# door_light.net
KiCad netlist of a schematic drawn in EAGLE
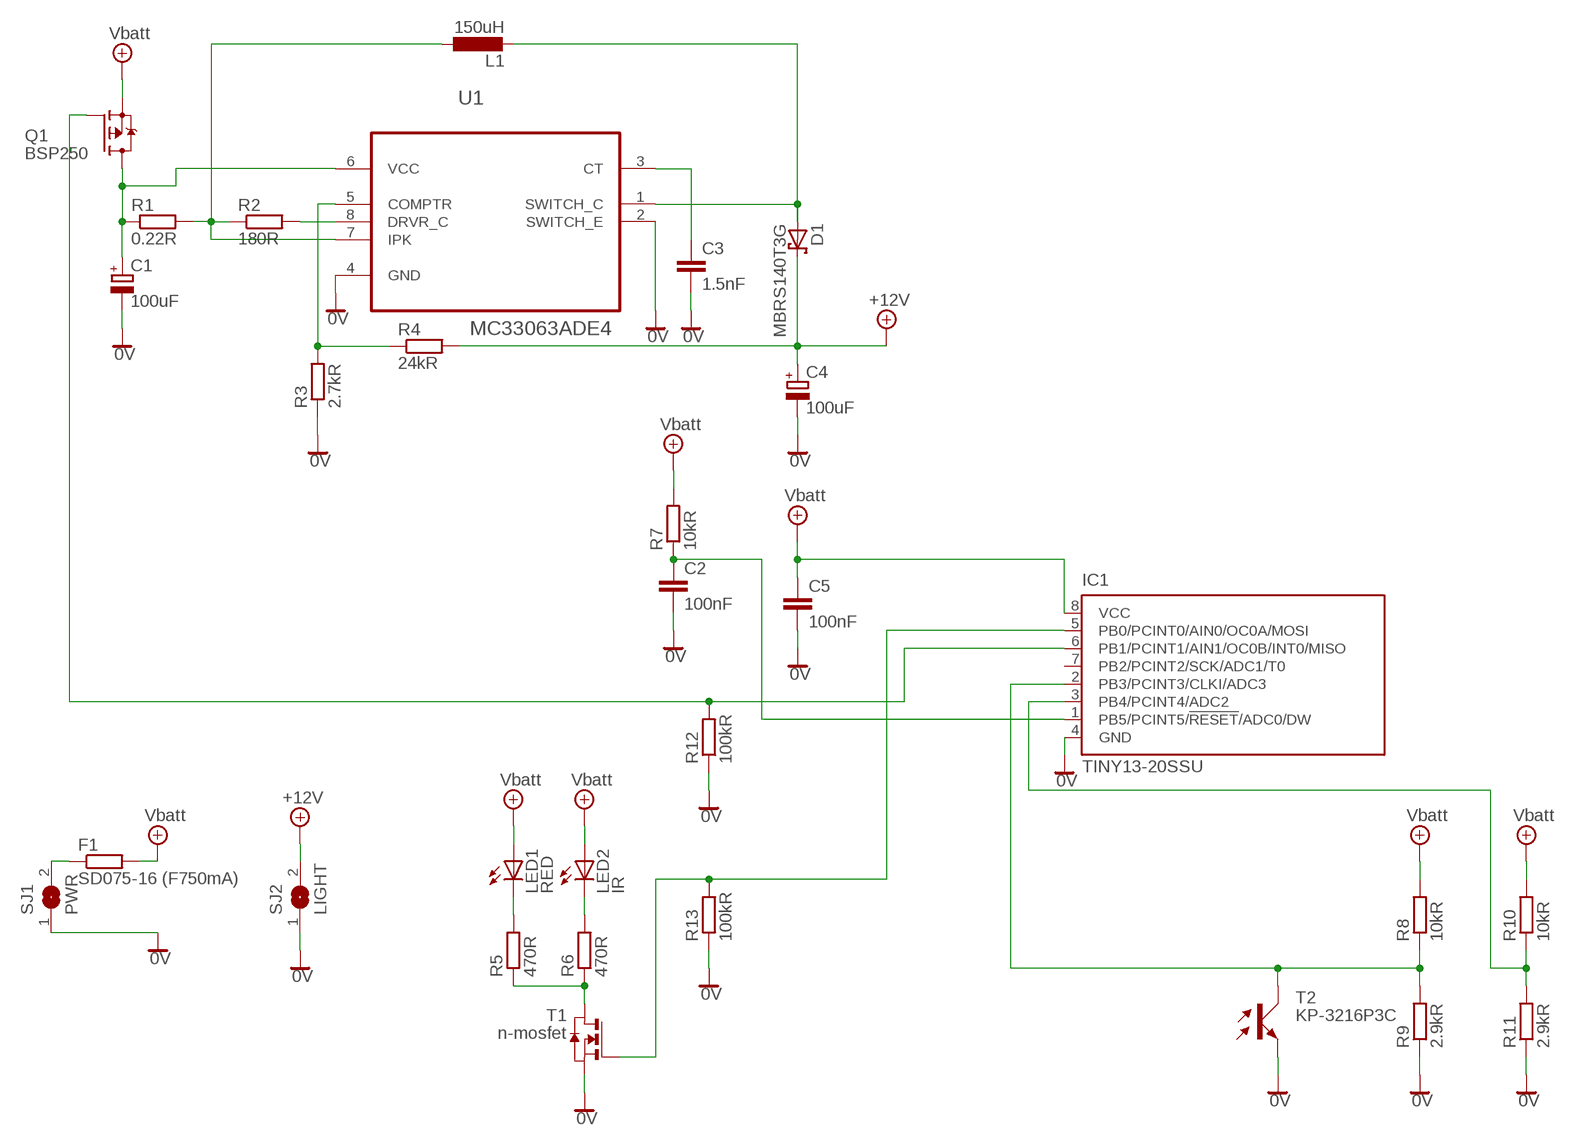
[diagram p0: schematic, sheet 1]

(export (version "E")
  (design (tool "Eeschema 10.0.6"))
  (components
    (comp (ref "C1")
      (value "100uF")
      (footprint "eagle-import:153CLV-0810")
      (libsource (lib "eagle-import") (part "CPOL-EU153CLV-0810"))
    )
    (comp (ref "C2")
      (value "100nF")
      (footprint "eagle-import:C1206")
      (libsource (lib "eagle-import") (part "C-EUC1206"))
    )
    (comp (ref "C3")
      (value "1.5nF")
      (footprint "eagle-import:C1206")
      (libsource (lib "eagle-import") (part "C-EUC1206"))
    )
    (comp (ref "C4")
      (value "100uF")
      (footprint "eagle-import:153CLV-0810")
      (libsource (lib "eagle-import") (part "CPOL-EU153CLV-0810"))
    )
    (comp (ref "C5")
      (value "100nF")
      (footprint "eagle-import:C1206")
      (libsource (lib "eagle-import") (part "C-EUC1206"))
    )
    (comp (ref "D1")
      (value "MBRS140T3G")
      (footprint "eagle-import:SMB")
      (libsource (lib "eagle-import") (part "MBRS130LT3"))
    )
    (comp (ref "F1")
      (value "SD075-16 (F750mA)")
      (footprint "eagle-import:MINI_MELF-0207W")
      (libsource (lib "eagle-import") (part "R-EU_MELF0207W"))
    )
    (comp (ref "IC1")
      (value "TINY13-20SSU")
      (footprint "eagle-import:8S1")
      (fields (field (name "MPN") "ATTINY13-20SSU"))
      (libsource (lib "eagle-import") (part "TINY13SSU-20"))
    )
    (comp (ref "L1")
      (value "150uH")
      (footprint "eagle-import:PIS2816")
      (libsource (lib "eagle-import") (part "L-EUPIS2816"))
    )
    (comp (ref "LED1")
      (value "RED")
      (footprint "eagle-import:CHIPLED_0603")
      (libsource (lib "eagle-import") (part "LEDCHIPLED_0603"))
    )
    (comp (ref "LED2")
      (value "IR")
      (footprint "eagle-import:CHIPLED_1206")
      (libsource (lib "eagle-import") (part "LEDCHIPLED_1206"))
    )
    (comp (ref "Q1")
      (value "BSP250")
      (footprint "eagle-import:SOT223")
      (libsource (lib "eagle-import") (part "BSP170P"))
    )
    (comp (ref "R1")
      (value "0.22R")
      (footprint "eagle-import:M1206")
      (libsource (lib "eagle-import") (part "R-EU_M1206"))
    )
    (comp (ref "R2")
      (value "180R")
      (footprint "eagle-import:R0603")
      (libsource (lib "eagle-import") (part "R-EU_R0603"))
    )
    (comp (ref "R3")
      (value "2.7kR")
      (footprint "eagle-import:R0603")
      (libsource (lib "eagle-import") (part "R-EU_R0603"))
    )
    (comp (ref "R4")
      (value "24kR")
      (footprint "eagle-import:R0603")
      (libsource (lib "eagle-import") (part "R-EU_R0603"))
    )
    (comp (ref "R5")
      (value "470R")
      (footprint "eagle-import:R0603")
      (libsource (lib "eagle-import") (part "R-EU_R0603"))
    )
    (comp (ref "R6")
      (value "470R")
      (footprint "eagle-import:R0603")
      (libsource (lib "eagle-import") (part "R-EU_R0603"))
    )
    (comp (ref "R7")
      (value "10kR")
      (footprint "eagle-import:R0402")
      (libsource (lib "eagle-import") (part "R-EU_R0402"))
    )
    (comp (ref "R8")
      (value "10kR")
      (footprint "eagle-import:R0603")
      (libsource (lib "eagle-import") (part "R-EU_R0603"))
    )
    (comp (ref "R9")
      (value "2.9kR")
      (footprint "eagle-import:R0603")
      (libsource (lib "eagle-import") (part "R-EU_R0603"))
    )
    (comp (ref "R10")
      (value "10kR")
      (footprint "eagle-import:R0603")
      (libsource (lib "eagle-import") (part "R-EU_R0603"))
    )
    (comp (ref "R11")
      (value "2.9kR")
      (footprint "eagle-import:R0603")
      (libsource (lib "eagle-import") (part "R-EU_R0603"))
    )
    (comp (ref "R12")
      (value "100kR")
      (footprint "eagle-import:R0603")
      (libsource (lib "eagle-import") (part "R-EU_R0603"))
    )
    (comp (ref "R13")
      (value "100kR")
      (footprint "eagle-import:R0603")
      (libsource (lib "eagle-import") (part "R-EU_R0603"))
    )
    (comp (ref "SJ1")
      (value "PWR")
      (footprint "eagle-import:SJW")
      (libsource (lib "eagle-import") (part "SJW"))
    )
    (comp (ref "SJ2")
      (value "LIGHT")
      (footprint "eagle-import:SJW")
      (libsource (lib "eagle-import") (part "SJW"))
    )
    (comp (ref "T1")
      (value "n-mosfet")
      (footprint "eagle-import:SOT-23")
      (libsource (lib "eagle-import") (part "NMOSSOT23"))
    )
    (comp (ref "T2")
      (value "KP-3216P3C")
      (footprint "eagle-import:OPTO-TRANS-SIEMENS_BP103")
      (libsource (lib "eagle-import") (part "KP-3216P3C"))
    )
    (comp (ref "U1")
      (value "MC33063ADE4")
      (footprint "eagle-import:SOIC127P600X175-8N")
      (libsource (lib "eagle-import") (part "MC33063ADE4"))
    )
  )
  (nets
    (net (code "1") (name "+12V") (class "Default")
      (node (ref "C4") (pin "+") (pinfunction "+_+") (pintype "passive"))
      (node (ref "D1") (pin "C") (pinfunction "C_C") (pintype "passive"))
      (node (ref "R4") (pin "2") (pinfunction "2_2") (pintype "passive"))
      (node (ref "SJ2") (pin "2") (pinfunction "2_2") (pintype "passive"))
    )
    (net (code "2") (name "0V") (class "Default")
      (node (ref "C1") (pin "-") (pinfunction "-_-") (pintype "passive"))
      (node (ref "C2") (pin "2") (pinfunction "2_2") (pintype "passive"))
      (node (ref "C3") (pin "2") (pinfunction "2_2") (pintype "passive"))
      (node (ref "C4") (pin "-") (pinfunction "-_-") (pintype "passive"))
      (node (ref "C5") (pin "2") (pinfunction "2_2") (pintype "passive"))
      (node (ref "IC1") (pin "4") (pinfunction "GND_4") (pintype "power_in"))
      (node (ref "R11") (pin "1") (pinfunction "1_1") (pintype "passive"))
      (node (ref "R12") (pin "1") (pinfunction "1_1") (pintype "passive"))
      (node (ref "R13") (pin "1") (pinfunction "1_1") (pintype "passive"))
      (node (ref "R3") (pin "1") (pinfunction "1_1") (pintype "passive"))
      (node (ref "R9") (pin "1") (pinfunction "1_1") (pintype "passive"))
      (node (ref "SJ1") (pin "1") (pinfunction "1_1") (pintype "passive"))
      (node (ref "SJ2") (pin "1") (pinfunction "1_1") (pintype "passive"))
      (node (ref "T1") (pin "2") (pinfunction "S_2") (pintype "passive"))
      (node (ref "T2") (pin "EMITER") (pinfunction "E_EMITER") (pintype "passive"))
      (node (ref "U1") (pin "2") (pinfunction "SWITCH_E_2") (pintype "passive"))
      (node (ref "U1") (pin "4") (pinfunction "GND_4") (pintype "passive"))
    )
    (net (code "3") (name "Net-(F1-Pad1)") (class "Default")
      (node (ref "F1") (pin "1") (pinfunction "1_1") (pintype "passive"))
      (node (ref "SJ1") (pin "2") (pinfunction "2_2") (pintype "passive"))
    )
    (net (code "4") (name "Net-(IC1-PB0{slash}PCINT0{slash}AIN0{slash}OC0A{slash}MOSI)") (class "Default")
      (node (ref "IC1") (pin "5") (pinfunction "PB0/PCINT0/AIN0/OC0A/MOSI_5") (pintype "bidirectional"))
      (node (ref "R13") (pin "2") (pinfunction "2_2") (pintype "passive"))
      (node (ref "T1") (pin "3") (pinfunction "G_3") (pintype "passive"))
    )
    (net (code "5") (name "Net-(IC1-PB1{slash}PCINT1{slash}AIN1{slash}OC0B{slash}INT0{slash}MISO)") (class "Default")
      (node (ref "IC1") (pin "6") (pinfunction "PB1/PCINT1/AIN1/OC0B/INT0/MISO_6") (pintype "bidirectional"))
      (node (ref "Q1") (pin "1") (pinfunction "G_1") (pintype "passive"))
      (node (ref "R12") (pin "2") (pinfunction "2_2") (pintype "passive"))
    )
    (net (code "6") (name "Net-(IC1-PB3{slash}PCINT3{slash}CLKI{slash}ADC3)") (class "Default")
      (node (ref "IC1") (pin "2") (pinfunction "PB3/PCINT3/CLKI/ADC3_2") (pintype "bidirectional"))
      (node (ref "R8") (pin "1") (pinfunction "1_1") (pintype "passive"))
      (node (ref "R9") (pin "2") (pinfunction "2_2") (pintype "passive"))
      (node (ref "T2") (pin "COLLECTOR") (pinfunction "C_COLLECTOR") (pintype "passive"))
    )
    (net (code "7") (name "Net-(IC1-PB4{slash}PCINT4{slash}ADC2)") (class "Default")
      (node (ref "IC1") (pin "3") (pinfunction "PB4/PCINT4/ADC2_3") (pintype "bidirectional"))
      (node (ref "R10") (pin "1") (pinfunction "1_1") (pintype "passive"))
      (node (ref "R11") (pin "2") (pinfunction "2_2") (pintype "passive"))
    )
    (net (code "8") (name "Net-(IC1-PB5{slash}PCINT5{slash}~{RESET}{slash}ADC0{slash}DW)") (class "Default")
      (node (ref "C2") (pin "1") (pinfunction "1_1") (pintype "passive"))
      (node (ref "IC1") (pin "1") (pinfunction "PB5/PCINT5/~{RESET}/ADC0/DW_1") (pintype "bidirectional"))
      (node (ref "R7") (pin "1") (pinfunction "1_1") (pintype "passive"))
    )
    (net (code "9") (name "Net-(LED1-PadC)") (class "Default")
      (node (ref "LED1") (pin "C") (pinfunction "C_C") (pintype "passive"))
      (node (ref "R5") (pin "2") (pinfunction "2_2") (pintype "passive"))
    )
    (net (code "10") (name "Net-(LED2-PadC)") (class "Default")
      (node (ref "LED2") (pin "C") (pinfunction "C_C") (pintype "passive"))
      (node (ref "R6") (pin "2") (pinfunction "2_2") (pintype "passive"))
    )
    (net (code "11") (name "Net-(T1-D)") (class "Default")
      (node (ref "R5") (pin "1") (pinfunction "1_1") (pintype "passive"))
      (node (ref "R6") (pin "1") (pinfunction "1_1") (pintype "passive"))
      (node (ref "T1") (pin "1") (pinfunction "D_1") (pintype "passive"))
    )
    (net (code "12") (name "Net-(U1-COMPTR)") (class "Default")
      (node (ref "R3") (pin "2") (pinfunction "2_2") (pintype "passive"))
      (node (ref "R4") (pin "1") (pinfunction "1_1") (pintype "passive"))
      (node (ref "U1") (pin "5") (pinfunction "COMPTR_5") (pintype "passive"))
    )
    (net (code "13") (name "Net-(U1-CT)") (class "Default")
      (node (ref "C3") (pin "1") (pinfunction "1_1") (pintype "passive"))
      (node (ref "U1") (pin "3") (pinfunction "CT_3") (pintype "passive"))
    )
    (net (code "14") (name "Net-(U1-DRVR_C)") (class "Default")
      (node (ref "R2") (pin "2") (pinfunction "2_2") (pintype "passive"))
      (node (ref "U1") (pin "8") (pinfunction "DRVR_C_8") (pintype "passive"))
    )
    (net (code "15") (name "Net-(U1-IPK)") (class "Default")
      (node (ref "L1") (pin "1") (pinfunction "1_1") (pintype "passive"))
      (node (ref "R1") (pin "2") (pinfunction "2_2") (pintype "passive"))
      (node (ref "R2") (pin "1") (pinfunction "1_1") (pintype "passive"))
      (node (ref "U1") (pin "7") (pinfunction "IPK_7") (pintype "passive"))
    )
    (net (code "16") (name "Net-(U1-SWITCH_C)") (class "Default")
      (node (ref "D1") (pin "A") (pinfunction "A_A") (pintype "passive"))
      (node (ref "L1") (pin "2") (pinfunction "2_2") (pintype "passive"))
      (node (ref "U1") (pin "1") (pinfunction "SWITCH_C_1") (pintype "passive"))
    )
    (net (code "17") (name "Net-(U1-VCC)") (class "Default")
      (node (ref "C1") (pin "+") (pinfunction "+_+") (pintype "passive"))
      (node (ref "Q1") (pin "2") (pinfunction "D_2") (pintype "passive"))
      (node (ref "Q1") (pin "4") (pinfunction "D_4") (pintype "passive"))
      (node (ref "R1") (pin "1") (pinfunction "1_1") (pintype "passive"))
      (node (ref "U1") (pin "6") (pinfunction "VCC_6") (pintype "power_in"))
    )
    (net (code "18") (name "Vbatt") (class "Default")
      (node (ref "C5") (pin "1") (pinfunction "1_1") (pintype "passive"))
      (node (ref "F1") (pin "2") (pinfunction "2_2") (pintype "passive"))
      (node (ref "IC1") (pin "8") (pinfunction "VCC_8") (pintype "power_in"))
      (node (ref "LED1") (pin "A") (pinfunction "A_A") (pintype "passive"))
      (node (ref "LED2") (pin "A") (pinfunction "A_A") (pintype "passive"))
      (node (ref "Q1") (pin "3") (pinfunction "S_3") (pintype "passive"))
      (node (ref "R10") (pin "2") (pinfunction "2_2") (pintype "passive"))
      (node (ref "R7") (pin "2") (pinfunction "2_2") (pintype "passive"))
      (node (ref "R8") (pin "2") (pinfunction "2_2") (pintype "passive"))
    )
    (net (code "19") (name "unconnected-(IC1-PB2{slash}PCINT2{slash}SCK{slash}ADC1{slash}T0-Pad7)") (class "Default")
      (node (ref "IC1") (pin "7") (pinfunction "PB2/PCINT2/SCK/ADC1/T0_7") (pintype "bidirectional"))
    )
  )
)
